# MCU_Sensors_CAN.net
KiCad netlist of a schematic drawn in Altium Designer
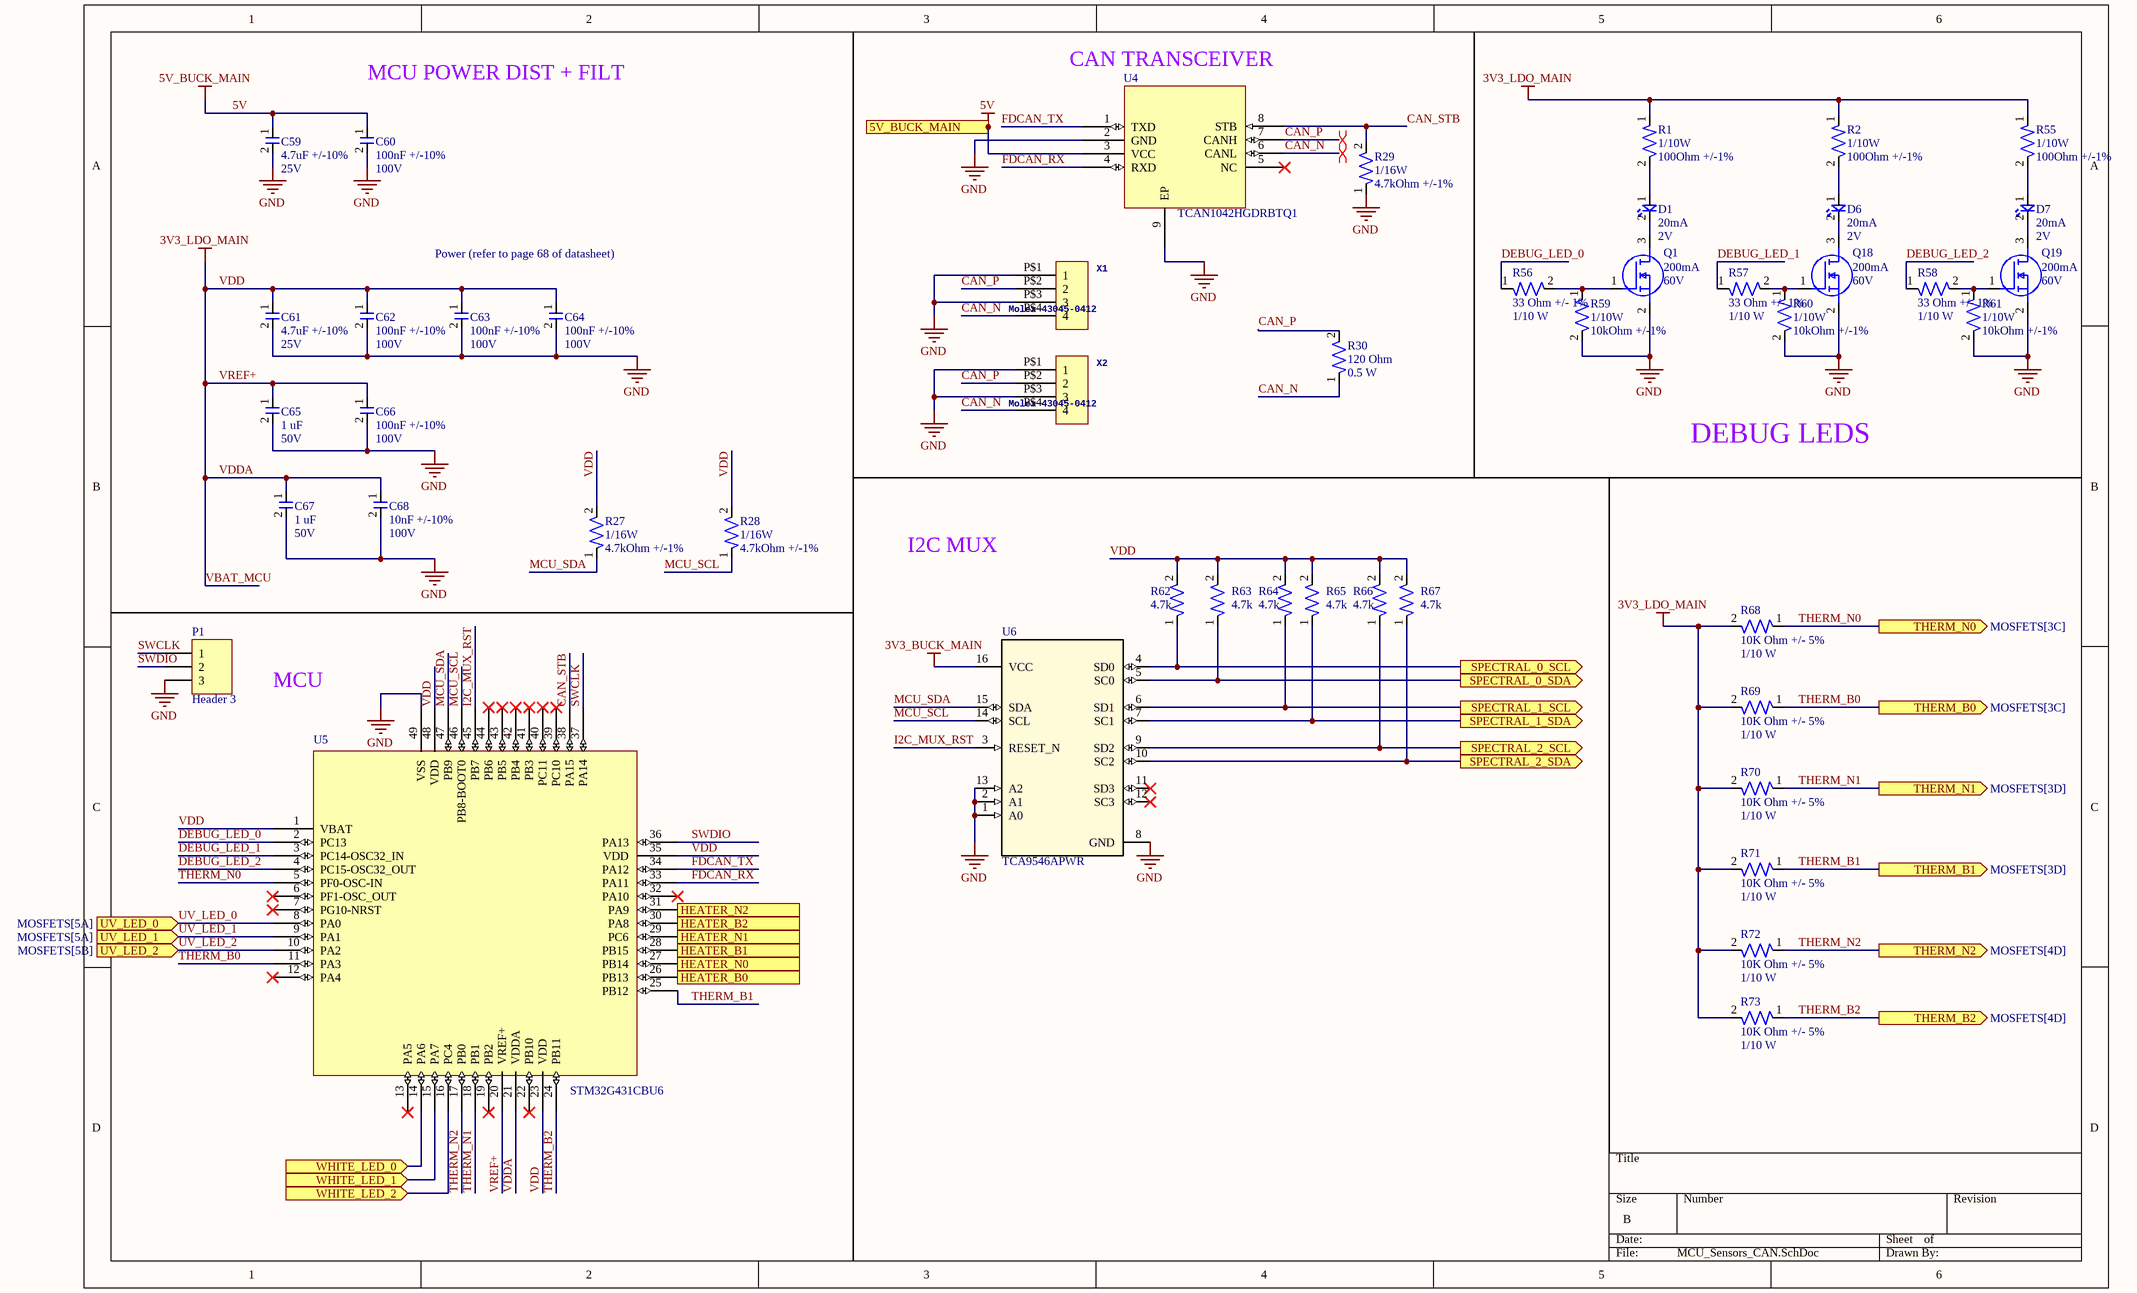
[diagram p0: MCU_Sensors_CAN.SchDoc]

(export (version "E")
  (design (tool "Eeschema 10.0.6"))
  (components
    (comp (ref "C59")
      (value "TMK107BBJ475KA-T")
      (footprint "CAP-0603")
      (description "4.7 µF ±10% 25V Ceramic Capacitor X5R 0603 (1608 Metric)")
      (fields
        (field (name "MANUFACTURER") "Taiyo Yuden")
        (field (name "CAPACITANCE") "4.7uF +/-10%")
        (field (name "VOLTAGE RATING") "25V")
      )
      (libsource (lib "MasterLib") (part "CAP-4.7U-0001"))
    )
    (comp (ref "C60")
      (value "CC0603KRX7R0BB104")
      (footprint "CAP-0603")
      (description "CAP CER 0.1UF 100V X7R 0603")
      (fields
        (field (name "MANUFACTURER") "YAGEO")
        (field (name "CAPACITANCE") "100nF +/-10%")
        (field (name "VOLTAGE RATING") "100V")
      )
      (libsource (lib "MasterLib") (part "CAP-100N-0001"))
    )
    (comp (ref "C61")
      (value "TMK107BBJ475KA-T")
      (footprint "CAP-0603")
      (description "4.7 µF ±10% 25V Ceramic Capacitor X5R 0603 (1608 Metric)")
      (fields
        (field (name "MANUFACTURER") "Taiyo Yuden")
        (field (name "CAPACITANCE") "4.7uF +/-10%")
        (field (name "VOLTAGE RATING") "25V")
      )
      (libsource (lib "MasterLib") (part "CAP-4.7U-0001"))
    )
    (comp (ref "C62")
      (value "CC0603KRX7R0BB104")
      (footprint "CAP-0603")
      (description "CAP CER 0.1UF 100V X7R 0603")
      (fields
        (field (name "MANUFACTURER") "YAGEO")
        (field (name "CAPACITANCE") "100nF +/-10%")
        (field (name "VOLTAGE RATING") "100V")
      )
      (libsource (lib "MasterLib") (part "CAP-100N-0001"))
    )
    (comp (ref "C63")
      (value "CC0603KRX7R0BB104")
      (footprint "CAP-0603")
      (description "CAP CER 0.1UF 100V X7R 0603")
      (fields
        (field (name "MANUFACTURER") "YAGEO")
        (field (name "CAPACITANCE") "100nF +/-10%")
        (field (name "VOLTAGE RATING") "100V")
      )
      (libsource (lib "MasterLib") (part "CAP-100N-0001"))
    )
    (comp (ref "C64")
      (value "CC0603KRX7R0BB104")
      (footprint "CAP-0603")
      (description "CAP CER 0.1UF 100V X7R 0603")
      (fields
        (field (name "MANUFACTURER") "YAGEO")
        (field (name "CAPACITANCE") "100nF +/-10%")
        (field (name "VOLTAGE RATING") "100V")
      )
      (libsource (lib "MasterLib") (part "CAP-100N-0001"))
    )
    (comp (ref "C65")
      (value "UMK107AB7105KA-T")
      (footprint "CAP-0603")
      (description "1 µF ±10% 50V Ceramic Capacitor X7R 0603 (1608 Metric)")
      (fields (field (name "CAPACITANCE") "1 uF") (field (name "VOLTAGE") "50V"))
      (libsource (lib "MasterLib") (part "CAP-1U-0002"))
    )
    (comp (ref "C66")
      (value "CC0603KRX7R0BB104")
      (footprint "CAP-0603")
      (description "CAP CER 0.1UF 100V X7R 0603")
      (fields
        (field (name "MANUFACTURER") "YAGEO")
        (field (name "CAPACITANCE") "100nF +/-10%")
        (field (name "VOLTAGE RATING") "100V")
      )
      (libsource (lib "MasterLib") (part "CAP-100N-0001"))
    )
    (comp (ref "C67")
      (value "UMK107AB7105KA-T")
      (footprint "CAP-0603")
      (description "1 µF ±10% 50V Ceramic Capacitor X7R 0603 (1608 Metric)")
      (fields (field (name "CAPACITANCE") "1 uF") (field (name "VOLTAGE") "50V"))
      (libsource (lib "MasterLib") (part "CAP-1U-0002"))
    )
    (comp (ref "C68")
      (value "CC0402KRX7R0BB103")
      (footprint "CAP-0402")
      (description "10000 pF ±10% 100V Ceramic Capacitor X7R 0402 (1005 Metric)")
      (fields
        (field (name "MANUFACTURER") "YAGEO")
        (field (name "CAPACITANCE") "10nF +/-10%")
        (field (name "VOLTAGE RATING") "100V")
      )
      (libsource (lib "MasterLib") (part "CAP-10N-0001"))
    )
    (comp (ref "D1")
      (value "150060AS75000")
      (footprint "LED-0603")
      (description "CAP CER 0.1UF 100V X7R 0603")
      (fields
        (field (name "MANUFACTURER") "Wurth Electronik")
        (field (name "CURRENT RATING") "20mA")
        (field (name "VF") "2V")
      )
      (libsource (lib "MasterLib") (part "LED_Amber_0001"))
    )
    (comp (ref "D6")
      (value "150060AS75000")
      (footprint "LED-0603")
      (description "CAP CER 0.1UF 100V X7R 0603")
      (fields
        (field (name "MANUFACTURER") "Wurth Electronik")
        (field (name "CURRENT RATING") "20mA")
        (field (name "VF") "2V")
      )
      (libsource (lib "MasterLib") (part "LED_Amber_0001"))
    )
    (comp (ref "D7")
      (value "150060AS75000")
      (footprint "LED-0603")
      (description "CAP CER 0.1UF 100V X7R 0603")
      (fields
        (field (name "MANUFACTURER") "Wurth Electronik")
        (field (name "CURRENT RATING") "20mA")
        (field (name "VF") "2V")
      )
      (libsource (lib "MasterLib") (part "LED_Amber_0001"))
    )
    (comp (ref "P1")
      (value "Header 3")
      (footprint "HDR1X3")
      (description "Header, 3-Pin")
      (fields (field (name "PUBLISHER") "Altium Limited"))
      (libsource (lib "Miscellaneous Connectors") (part "Header 3"))
    )
    (comp (ref "Q1")
      (value "T2N7002AK,LM")
      (footprint "NMOS-SOT23-3")
      (description "MOSFET N-CH 60V 200MA SOT23")
      (fields
        (field (name "MANUFACTURER") "Toshiba")
        (field (name "ID-CONTINUOUS") "200mA")
        (field (name "VDS-MAX") "60V")
      )
      (libsource (lib "MasterLib") (part "NMOS-200MA-0001"))
    )
    (comp (ref "Q18")
      (value "T2N7002AK,LM")
      (footprint "NMOS-SOT23-3")
      (description "MOSFET N-CH 60V 200MA SOT23")
      (fields
        (field (name "MANUFACTURER") "Toshiba")
        (field (name "ID-CONTINUOUS") "200mA")
        (field (name "VDS-MAX") "60V")
      )
      (libsource (lib "MasterLib") (part "NMOS-200MA-0001"))
    )
    (comp (ref "Q19")
      (value "T2N7002AK,LM")
      (footprint "NMOS-SOT23-3")
      (description "MOSFET N-CH 60V 200MA SOT23")
      (fields
        (field (name "MANUFACTURER") "Toshiba")
        (field (name "ID-CONTINUOUS") "200mA")
        (field (name "VDS-MAX") "60V")
      )
      (libsource (lib "MasterLib") (part "NMOS-200MA-0001"))
    )
    (comp (ref "R1")
      (value "AC0603FR-10100RL")
      (footprint "RES-0603")
      (description "100 Ohms ±1% 0.1W, 1/10W Chip Resistor 0603 (1608 Metric) Automotive AEC-Q200 Thick Film")
      (fields
        (field (name "MANUFACTURER") "YAGEO")
        (field (name "POWER RATING") "1/10W")
        (field (name "RESISTANCE") "100Ohm +/-1%")
      )
      (libsource (lib "MasterLib") (part "RES-100-0002"))
    )
    (comp (ref "R2")
      (value "AC0603FR-10100RL")
      (footprint "RES-0603")
      (description "100 Ohms ±1% 0.1W, 1/10W Chip Resistor 0603 (1608 Metric) Automotive AEC-Q200 Thick Film")
      (fields
        (field (name "MANUFACTURER") "YAGEO")
        (field (name "POWER RATING") "1/10W")
        (field (name "RESISTANCE") "100Ohm +/-1%")
      )
      (libsource (lib "MasterLib") (part "RES-100-0002"))
    )
    (comp (ref "R27")
      (value "RC0402FR-074K7P")
      (footprint "RES-0402")
      (description "RES SMD 4.7K OHM 1% 1/16W 0402")
      (fields
        (field (name "MANUFACTURER") "YAGEO")
        (field (name "POWER RATING") "1/16W")
        (field (name "RESISTANCE") "4.7kOhm +/-1%")
      )
      (libsource (lib "MasterLib") (part "RES-4.7K-0001"))
    )
    (comp (ref "R28")
      (value "RC0402FR-074K7P")
      (footprint "RES-0402")
      (description "RES SMD 4.7K OHM 1% 1/16W 0402")
      (fields
        (field (name "MANUFACTURER") "YAGEO")
        (field (name "POWER RATING") "1/16W")
        (field (name "RESISTANCE") "4.7kOhm +/-1%")
      )
      (libsource (lib "MasterLib") (part "RES-4.7K-0001"))
    )
    (comp (ref "R29")
      (value "RC0402FR-074K7P")
      (footprint "RES-0402")
      (description "RES SMD 4.7K OHM 1% 1/16W 0402")
      (fields
        (field (name "MANUFACTURER") "YAGEO")
        (field (name "POWER RATING") "1/16W")
        (field (name "RESISTANCE") "4.7kOhm +/-1%")
      )
      (libsource (lib "MasterLib") (part "RES-4.7K-0001"))
    )
    (comp (ref "R30")
      (value "CRGH1206F120R")
      (footprint "RES-1206")
      (description "120 Ohms ±1% 0.5W, 1/2W Chip Resistor 1206 (3216 Metric) Thick Film")
      (fields
        (field (name "TOLERANCE") "1%")
        (field (name "RESISTANCE") "120 Ohm")
        (field (name "POWER") "0.5 W")
      )
      (libsource (lib "MasterLib") (part "RES-120-0002"))
    )
    (comp (ref "R55")
      (value "AC0603FR-10100RL")
      (footprint "RES-0603")
      (description "100 Ohms ±1% 0.1W, 1/10W Chip Resistor 0603 (1608 Metric) Automotive AEC-Q200 Thick Film")
      (fields
        (field (name "MANUFACTURER") "YAGEO")
        (field (name "POWER RATING") "1/10W")
        (field (name "RESISTANCE") "100Ohm +/-1%")
      )
      (libsource (lib "MasterLib") (part "RES-100-0002"))
    )
    (comp (ref "R56")
      (value "ERJ2RKF33R0X")
      (footprint "RES-0402")
      (description "100mW Thick Film Resistors ±100ppm/℃ ±1% -55℃~+155℃ 33Ω 0402  Chip Resistor - Surface Mount ROHS")
      (fields
        (field (name "RESISTANCE") "33 Ohm +/- 1%")
        (field (name "POWER") "1/10 W")
        (field (name "JLC PART NUMBER") "C278594")
      )
      (libsource (lib "MasterLib") (part "RES-33-0003-JLC"))
    )
    (comp (ref "R57")
      (value "ERJ2RKF33R0X")
      (footprint "RES-0402")
      (description "100mW Thick Film Resistors ±100ppm/℃ ±1% -55℃~+155℃ 33Ω 0402  Chip Resistor - Surface Mount ROHS")
      (fields
        (field (name "RESISTANCE") "33 Ohm +/- 1%")
        (field (name "POWER") "1/10 W")
        (field (name "JLC PART NUMBER") "C278594")
      )
      (libsource (lib "MasterLib") (part "RES-33-0003-JLC"))
    )
    (comp (ref "R58")
      (value "ERJ2RKF33R0X")
      (footprint "RES-0402")
      (description "100mW Thick Film Resistors ±100ppm/℃ ±1% -55℃~+155℃ 33Ω 0402  Chip Resistor - Surface Mount ROHS")
      (fields
        (field (name "RESISTANCE") "33 Ohm +/- 1%")
        (field (name "POWER") "1/10 W")
        (field (name "JLC PART NUMBER") "C278594")
      )
      (libsource (lib "MasterLib") (part "RES-33-0003-JLC"))
    )
    (comp (ref "R59")
      (value "RC0603FR-0710KP")
      (footprint "RES-0603")
      (description "RES SMD 10K OHM 1% 1/10W 0603")
      (fields
        (field (name "MANUFACTURER") "YAGEO")
        (field (name "POWER RATING") "1/10W")
        (field (name "RESISTANCE") "10kOhm +/-1%")
      )
      (libsource (lib "MasterLib") (part "RES-10K-0002"))
    )
    (comp (ref "R60")
      (value "RC0603FR-0710KP")
      (footprint "RES-0603")
      (description "RES SMD 10K OHM 1% 1/10W 0603")
      (fields
        (field (name "MANUFACTURER") "YAGEO")
        (field (name "POWER RATING") "1/10W")
        (field (name "RESISTANCE") "10kOhm +/-1%")
      )
      (libsource (lib "MasterLib") (part "RES-10K-0002"))
    )
    (comp (ref "R61")
      (value "RC0603FR-0710KP")
      (footprint "RES-0603")
      (description "RES SMD 10K OHM 1% 1/10W 0603")
      (fields
        (field (name "MANUFACTURER") "YAGEO")
        (field (name "POWER RATING") "1/10W")
        (field (name "RESISTANCE") "10kOhm +/-1%")
      )
      (libsource (lib "MasterLib") (part "RES-10K-0002"))
    )
    (comp (ref "R62")
      (value "RC0402FR-074K7P")
      (footprint "RES-0402")
      (description "RES SMD 4.7K OHM 1% 1/16W 0402")
      (fields (field (name "MANUFACTURER") "YAGEO") (field (name "RESISTANCE") "4.7k"))
      (libsource (lib "MasterLib") (part "RES-4.7K-0001"))
    )
    (comp (ref "R63")
      (value "RC0402FR-074K7P")
      (footprint "RES-0402")
      (description "RES SMD 4.7K OHM 1% 1/16W 0402")
      (fields (field (name "MANUFACTURER") "YAGEO") (field (name "RESISTANCE") "4.7k"))
      (libsource (lib "MasterLib") (part "RES-4.7K-0001"))
    )
    (comp (ref "R64")
      (value "RC0402FR-074K7P")
      (footprint "RES-0402")
      (description "RES SMD 4.7K OHM 1% 1/16W 0402")
      (fields (field (name "MANUFACTURER") "YAGEO") (field (name "RESISTANCE") "4.7k"))
      (libsource (lib "MasterLib") (part "RES-4.7K-0001"))
    )
    (comp (ref "R65")
      (value "RC0402FR-074K7P")
      (footprint "RES-0402")
      (description "RES SMD 4.7K OHM 1% 1/16W 0402")
      (fields (field (name "MANUFACTURER") "YAGEO") (field (name "RESISTANCE") "4.7k"))
      (libsource (lib "MasterLib") (part "RES-4.7K-0001"))
    )
    (comp (ref "R66")
      (value "RC0402FR-074K7P")
      (footprint "RES-0402")
      (description "RES SMD 4.7K OHM 1% 1/16W 0402")
      (fields (field (name "MANUFACTURER") "YAGEO") (field (name "RESISTANCE") "4.7k"))
      (libsource (lib "MasterLib") (part "RES-4.7K-0001"))
    )
    (comp (ref "R67")
      (value "RC0402FR-074K7P")
      (footprint "RES-0402")
      (description "RES SMD 4.7K OHM 1% 1/16W 0402")
      (fields (field (name "MANUFACTURER") "YAGEO") (field (name "RESISTANCE") "4.7k"))
      (libsource (lib "MasterLib") (part "RES-4.7K-0001"))
    )
    (comp (ref "R68")
      (value "ERJ2GEJ103X")
      (footprint "RES-0402")
      (fields
        (field (name "RESISTANCE") "10K Ohm +/- 5%")
        (field (name "POWER") "1/10 W")
        (field (name "JLC PART NUMBER") "C278577")
      )
      (libsource (lib "MasterLib") (part "RES-10K-0003-JLC"))
    )
    (comp (ref "R69")
      (value "ERJ2GEJ103X")
      (footprint "RES-0402")
      (fields
        (field (name "RESISTANCE") "10K Ohm +/- 5%")
        (field (name "POWER") "1/10 W")
        (field (name "JLC PART NUMBER") "C278577")
      )
      (libsource (lib "MasterLib") (part "RES-10K-0003-JLC"))
    )
    (comp (ref "R70")
      (value "ERJ2GEJ103X")
      (footprint "RES-0402")
      (fields
        (field (name "RESISTANCE") "10K Ohm +/- 5%")
        (field (name "POWER") "1/10 W")
        (field (name "JLC PART NUMBER") "C278577")
      )
      (libsource (lib "MasterLib") (part "RES-10K-0003-JLC"))
    )
    (comp (ref "R71")
      (value "ERJ2GEJ103X")
      (footprint "RES-0402")
      (fields
        (field (name "RESISTANCE") "10K Ohm +/- 5%")
        (field (name "POWER") "1/10 W")
        (field (name "JLC PART NUMBER") "C278577")
      )
      (libsource (lib "MasterLib") (part "RES-10K-0003-JLC"))
    )
    (comp (ref "R72")
      (value "ERJ2GEJ103X")
      (footprint "RES-0402")
      (fields
        (field (name "RESISTANCE") "10K Ohm +/- 5%")
        (field (name "POWER") "1/10 W")
        (field (name "JLC PART NUMBER") "C278577")
      )
      (libsource (lib "MasterLib") (part "RES-10K-0003-JLC"))
    )
    (comp (ref "R73")
      (value "ERJ2GEJ103X")
      (footprint "RES-0402")
      (fields
        (field (name "RESISTANCE") "10K Ohm +/- 5%")
        (field (name "POWER") "1/10 W")
        (field (name "JLC PART NUMBER") "C278577")
      )
      (libsource (lib "MasterLib") (part "RES-10K-0003-JLC"))
    )
    (comp (ref "U4")
      (value "TCAN1042HGDRBTQ1")
      (footprint "IC-8-VSON")
      (description "1/1 Transceiver CANbus 8-VSON (3x3)")
      (fields (field (name "MANUFACTURER") "Texas Instrument"))
      (libsource (lib "MasterLib") (part "IC-CAN-TRANSCEIVER-0002"))
    )
    (comp (ref "U5")
      (value "STM32G431CBU6")
      (footprint "MCU-UFQFPN48")
      (libsource (lib "MasterLib") (part "IC-STM32G431CBU6"))
    )
    (comp (ref "U6")
      (value "TCA9546APWR")
      (footprint "PW0016A-IPC_A")
      (description "Multiplexer Switch ICs I2C SWITCH 4CH")
      (fields (field (name "COPYRIGHT") "Copyright (C) 2023 Ultra Librarian. All rights reserved."))
      (libsource (lib "MasterLib") (part "IC-MUX-0003"))
    )
    (comp (ref "X1")
      (value "Molex 43045-0412")
      (footprint "43045-0412")
      (libsource (lib "Molex Microfit") (part "Micro-Fit Molex 4 Pin 2 Row Vertical"))
    )
    (comp (ref "X2")
      (value "Molex 43045-0412")
      (footprint "43045-0412")
      (libsource (lib "Molex Microfit") (part "Micro-Fit Molex 4 Pin 2 Row Vertical"))
    )
  )
  (nets
    (net (code "1") (name "/CAN_N") (class "Default")
      (node (ref "R30") (pin "1") (pinfunction "1_1") (pintype "passive"))
      (node (ref "U4") (pin "6") (pinfunction "CANL_6") (pintype "bidirectional"))
      (node (ref "X1") (pin "P$4") (pinfunction "4_P$4") (pintype "passive"))
      (node (ref "X2") (pin "P$4") (pinfunction "4_P$4") (pintype "passive"))
    )
    (net (code "2") (name "/CAN_P") (class "Default")
      (node (ref "R30") (pin "2") (pinfunction "2_2") (pintype "passive"))
      (node (ref "U4") (pin "7") (pinfunction "CANH_7") (pintype "bidirectional"))
      (node (ref "X1") (pin "P$2") (pinfunction "2_P$2") (pintype "passive"))
      (node (ref "X2") (pin "P$2") (pinfunction "2_P$2") (pintype "passive"))
    )
    (net (code "3") (name "/CAN_STB") (class "Default")
      (node (ref "R29") (pin "2") (pinfunction "2_2") (pintype "passive"))
      (node (ref "U4") (pin "8") (pinfunction "STB_8") (pintype "input"))
      (node (ref "U5") (pin "38") (pinfunction "PA15_38") (pintype "bidirectional"))
    )
    (net (code "4") (name "/DEBUG_LED_0") (class "Default")
      (node (ref "R56") (pin "1") (pinfunction "1_1") (pintype "passive"))
      (node (ref "U5") (pin "2") (pinfunction "PC13_2") (pintype "bidirectional"))
    )
    (net (code "5") (name "/DEBUG_LED_1") (class "Default")
      (node (ref "R57") (pin "1") (pinfunction "1_1") (pintype "passive"))
      (node (ref "U5") (pin "3") (pinfunction "PC14-OSC32_IN_3") (pintype "bidirectional"))
    )
    (net (code "6") (name "/DEBUG_LED_2") (class "Default")
      (node (ref "R58") (pin "1") (pinfunction "1_1") (pintype "passive"))
      (node (ref "U5") (pin "4") (pinfunction "PC15-OSC32_OUT_4") (pintype "bidirectional"))
    )
    (net (code "7") (name "/FDCAN_RX") (class "Default")
      (node (ref "U4") (pin "4") (pinfunction "RXD_4") (pintype "bidirectional"))
      (node (ref "U5") (pin "33") (pinfunction "PA11_33") (pintype "bidirectional"))
    )
    (net (code "8") (name "/FDCAN_TX") (class "Default")
      (node (ref "U4") (pin "1") (pinfunction "TXD_1") (pintype "bidirectional"))
      (node (ref "U5") (pin "34") (pinfunction "PA12_34") (pintype "bidirectional"))
    )
    (net (code "9") (name "/HEATER_B0") (class "Default")
      (node (ref "U5") (pin "26") (pinfunction "PB13_26") (pintype "bidirectional"))
    )
    (net (code "10") (name "/HEATER_B1") (class "Default")
      (node (ref "U5") (pin "28") (pinfunction "PB15_28") (pintype "bidirectional"))
    )
    (net (code "11") (name "/HEATER_B2") (class "Default")
      (node (ref "U5") (pin "30") (pinfunction "PA8_30") (pintype "bidirectional"))
    )
    (net (code "12") (name "/HEATER_N0") (class "Default")
      (node (ref "U5") (pin "27") (pinfunction "PB14_27") (pintype "bidirectional"))
    )
    (net (code "13") (name "/HEATER_N1") (class "Default")
      (node (ref "U5") (pin "29") (pinfunction "PC6_29") (pintype "bidirectional"))
    )
    (net (code "14") (name "/HEATER_N2") (class "Default")
      (node (ref "U5") (pin "31") (pinfunction "PA9_31") (pintype "bidirectional"))
    )
    (net (code "15") (name "/I2C_MUX_RST") (class "Default")
      (node (ref "U5") (pin "45") (pinfunction "PB7_45") (pintype "bidirectional"))
      (node (ref "U6") (pin "3") (pinfunction "RESET_N_3") (pintype "input"))
    )
    (net (code "16") (name "/MCU_SCL") (class "Default")
      (node (ref "R28") (pin "1") (pinfunction "1_1") (pintype "passive"))
      (node (ref "U5") (pin "46") (pinfunction "PB8-BOOT0_46") (pintype "bidirectional"))
      (node (ref "U6") (pin "14") (pinfunction "SCL_14") (pintype "bidirectional"))
    )
    (net (code "17") (name "/MCU_SDA") (class "Default")
      (node (ref "R27") (pin "1") (pinfunction "1_1") (pintype "passive"))
      (node (ref "U5") (pin "47") (pinfunction "PB9_47") (pintype "bidirectional"))
      (node (ref "U6") (pin "15") (pinfunction "SDA_15") (pintype "bidirectional"))
    )
    (net (code "18") (name "/SPECTRAL_0_SCL") (class "Default")
      (node (ref "R62") (pin "1") (pinfunction "1_1") (pintype "passive"))
      (node (ref "U6") (pin "4") (pinfunction "SD0_4") (pintype "bidirectional"))
    )
    (net (code "19") (name "/SPECTRAL_0_SDA") (class "Default")
      (node (ref "R63") (pin "1") (pinfunction "1_1") (pintype "passive"))
      (node (ref "U6") (pin "5") (pinfunction "SC0_5") (pintype "bidirectional"))
    )
    (net (code "20") (name "/SPECTRAL_1_SCL") (class "Default")
      (node (ref "R64") (pin "1") (pinfunction "1_1") (pintype "passive"))
      (node (ref "U6") (pin "6") (pinfunction "SD1_6") (pintype "bidirectional"))
    )
    (net (code "21") (name "/SPECTRAL_1_SDA") (class "Default")
      (node (ref "R65") (pin "1") (pinfunction "1_1") (pintype "passive"))
      (node (ref "U6") (pin "7") (pinfunction "SC1_7") (pintype "bidirectional"))
    )
    (net (code "22") (name "/SPECTRAL_2_SCL") (class "Default")
      (node (ref "R66") (pin "1") (pinfunction "1_1") (pintype "passive"))
      (node (ref "U6") (pin "9") (pinfunction "SD2_9") (pintype "bidirectional"))
    )
    (net (code "23") (name "/SPECTRAL_2_SDA") (class "Default")
      (node (ref "R67") (pin "1") (pinfunction "1_1") (pintype "passive"))
      (node (ref "U6") (pin "10") (pinfunction "SC2_10") (pintype "bidirectional"))
    )
    (net (code "24") (name "/SWCLK") (class "Default")
      (node (ref "P1") (pin "1") (pinfunction "1_1") (pintype "passive"))
      (node (ref "U5") (pin "37") (pinfunction "PA14_37") (pintype "bidirectional"))
    )
    (net (code "25") (name "/SWDIO") (class "Default")
      (node (ref "P1") (pin "2") (pinfunction "2_2") (pintype "passive"))
      (node (ref "U5") (pin "36") (pinfunction "PA13_36") (pintype "bidirectional"))
    )
    (net (code "26") (name "/THERM_B0") (class "Default")
      (node (ref "R69") (pin "1") (pinfunction "1_1") (pintype "passive"))
      (node (ref "U5") (pin "11") (pinfunction "PA3_11") (pintype "bidirectional"))
    )
    (net (code "27") (name "/THERM_B1") (class "Default")
      (node (ref "R71") (pin "1") (pinfunction "1_1") (pintype "passive"))
      (node (ref "U5") (pin "25") (pinfunction "PB12_25") (pintype "bidirectional"))
    )
    (net (code "28") (name "/THERM_B2") (class "Default")
      (node (ref "R73") (pin "1") (pinfunction "1_1") (pintype "passive"))
      (node (ref "U5") (pin "24") (pinfunction "PB11_24") (pintype "bidirectional"))
    )
    (net (code "29") (name "/THERM_N0") (class "Default")
      (node (ref "R68") (pin "1") (pinfunction "1_1") (pintype "passive"))
      (node (ref "U5") (pin "5") (pinfunction "PF0-OSC-IN_5") (pintype "bidirectional"))
    )
    (net (code "30") (name "/THERM_N1") (class "Default")
      (node (ref "R70") (pin "1") (pinfunction "1_1") (pintype "passive"))
      (node (ref "U5") (pin "18") (pinfunction "PB1_18") (pintype "bidirectional"))
    )
    (net (code "31") (name "/THERM_N2") (class "Default")
      (node (ref "R72") (pin "1") (pinfunction "1_1") (pintype "passive"))
      (node (ref "U5") (pin "17") (pinfunction "PB0_17") (pintype "bidirectional"))
    )
    (net (code "32") (name "/UV_LED_0") (class "Default")
      (node (ref "U5") (pin "8") (pinfunction "PA0_8") (pintype "bidirectional"))
    )
    (net (code "33") (name "/UV_LED_1") (class "Default")
      (node (ref "U5") (pin "9") (pinfunction "PA1_9") (pintype "bidirectional"))
    )
    (net (code "34") (name "/UV_LED_2") (class "Default")
      (node (ref "U5") (pin "10") (pinfunction "PA2_10") (pintype "bidirectional"))
    )
    (net (code "35") (name "/WHITE_LED_0") (class "Default")
      (node (ref "U5") (pin "14") (pinfunction "PA6_14") (pintype "bidirectional"))
    )
    (net (code "36") (name "/WHITE_LED_1") (class "Default")
      (node (ref "U5") (pin "15") (pinfunction "PA7_15") (pintype "bidirectional"))
    )
    (net (code "37") (name "/WHITE_LED_2") (class "Default")
      (node (ref "U5") (pin "16") (pinfunction "PC4_16") (pintype "bidirectional"))
    )
    (net (code "38") (name "3V3_BUCK_MAIN") (class "Default")
      (node (ref "U6") (pin "16") (pinfunction "VCC_16") (pintype "power_in"))
    )
    (net (code "39") (name "3V3_LDO_MAIN") (class "Default")
      (node (ref "C61") (pin "1") (pinfunction "1_1") (pintype "passive"))
      (node (ref "C62") (pin "1") (pinfunction "1_1") (pintype "passive"))
      (node (ref "C63") (pin "1") (pinfunction "1_1") (pintype "passive"))
      (node (ref "C64") (pin "1") (pinfunction "1_1") (pintype "passive"))
      (node (ref "C65") (pin "1") (pinfunction "1_1") (pintype "passive"))
      (node (ref "C66") (pin "1") (pinfunction "1_1") (pintype "passive"))
      (node (ref "C67") (pin "1") (pinfunction "1_1") (pintype "passive"))
      (node (ref "C68") (pin "1") (pinfunction "1_1") (pintype "passive"))
      (node (ref "R1") (pin "1") (pinfunction "1_1") (pintype "passive"))
      (node (ref "R2") (pin "1") (pinfunction "1_1") (pintype "passive"))
      (node (ref "R27") (pin "2") (pinfunction "2_2") (pintype "passive"))
      (node (ref "R28") (pin "2") (pinfunction "2_2") (pintype "passive"))
      (node (ref "R55") (pin "1") (pinfunction "1_1") (pintype "passive"))
      (node (ref "R62") (pin "2") (pinfunction "2_2") (pintype "passive"))
      (node (ref "R63") (pin "2") (pinfunction "2_2") (pintype "passive"))
      (node (ref "R64") (pin "2") (pinfunction "2_2") (pintype "passive"))
      (node (ref "R65") (pin "2") (pinfunction "2_2") (pintype "passive"))
      (node (ref "R66") (pin "2") (pinfunction "2_2") (pintype "passive"))
      (node (ref "R67") (pin "2") (pinfunction "2_2") (pintype "passive"))
      (node (ref "R68") (pin "2") (pinfunction "2_2") (pintype "passive"))
      (node (ref "R69") (pin "2") (pinfunction "2_2") (pintype "passive"))
      (node (ref "R70") (pin "2") (pinfunction "2_2") (pintype "passive"))
      (node (ref "R71") (pin "2") (pinfunction "2_2") (pintype "passive"))
      (node (ref "R72") (pin "2") (pinfunction "2_2") (pintype "passive"))
      (node (ref "R73") (pin "2") (pinfunction "2_2") (pintype "passive"))
      (node (ref "U5") (pin "1") (pinfunction "VBAT_1") (pintype "power_in"))
      (node (ref "U5") (pin "20") (pinfunction "VREF+_20") (pintype "power_in"))
      (node (ref "U5") (pin "21") (pinfunction "VDDA_21") (pintype "power_in"))
      (node (ref "U5") (pin "23") (pinfunction "VDD_23") (pintype "power_in"))
      (node (ref "U5") (pin "35") (pinfunction "VDD_35") (pintype "power_in"))
      (node (ref "U5") (pin "48") (pinfunction "VDD_48") (pintype "power_in"))
    )
    (net (code "40") (name "5V") (class "Default")
      (node (ref "C59") (pin "1") (pinfunction "1_1") (pintype "passive"))
      (node (ref "C60") (pin "1") (pinfunction "1_1") (pintype "passive"))
      (node (ref "U4") (pin "3") (pinfunction "VCC_3") (pintype "power_in"))
    )
    (net (code "41") (name "GND") (class "Default")
      (node (ref "C59") (pin "2") (pinfunction "2_2") (pintype "passive"))
      (node (ref "C60") (pin "2") (pinfunction "2_2") (pintype "passive"))
      (node (ref "C61") (pin "2") (pinfunction "2_2") (pintype "passive"))
      (node (ref "C62") (pin "2") (pinfunction "2_2") (pintype "passive"))
      (node (ref "C63") (pin "2") (pinfunction "2_2") (pintype "passive"))
      (node (ref "C64") (pin "2") (pinfunction "2_2") (pintype "passive"))
      (node (ref "C65") (pin "2") (pinfunction "2_2") (pintype "passive"))
      (node (ref "C66") (pin "2") (pinfunction "2_2") (pintype "passive"))
      (node (ref "C67") (pin "2") (pinfunction "2_2") (pintype "passive"))
      (node (ref "C68") (pin "2") (pinfunction "2_2") (pintype "passive"))
      (node (ref "P1") (pin "3") (pinfunction "3_3") (pintype "passive"))
      (node (ref "Q1") (pin "2") (pinfunction "S_2") (pintype "passive"))
      (node (ref "Q18") (pin "2") (pinfunction "S_2") (pintype "passive"))
      (node (ref "Q19") (pin "2") (pinfunction "S_2") (pintype "passive"))
      (node (ref "R29") (pin "1") (pinfunction "1_1") (pintype "passive"))
      (node (ref "R59") (pin "2") (pinfunction "2_2") (pintype "passive"))
      (node (ref "R60") (pin "2") (pinfunction "2_2") (pintype "passive"))
      (node (ref "R61") (pin "2") (pinfunction "2_2") (pintype "passive"))
      (node (ref "U4") (pin "2") (pinfunction "GND_2") (pintype "power_in"))
      (node (ref "U4") (pin "9") (pinfunction "EP_9") (pintype "power_in"))
      (node (ref "U5") (pin "49") (pinfunction "VSS_49") (pintype "power_in"))
      (node (ref "U6") (pin "1") (pinfunction "A0_1") (pintype "input"))
      (node (ref "U6") (pin "13") (pinfunction "A2_13") (pintype "input"))
      (node (ref "U6") (pin "2") (pinfunction "A1_2") (pintype "input"))
      (node (ref "U6") (pin "8") (pinfunction "GND_8") (pintype "power_in"))
      (node (ref "X1") (pin "P$1") (pinfunction "1_P$1") (pintype "passive"))
      (node (ref "X1") (pin "P$3") (pinfunction "3_P$3") (pintype "passive"))
      (node (ref "X2") (pin "P$1") (pinfunction "1_P$1") (pintype "passive"))
      (node (ref "X2") (pin "P$3") (pinfunction "3_P$3") (pintype "passive"))
    )
    (net (code "42") (name "Net-(D1-Pad1)") (class "Default")
      (node (ref "D1") (pin "1") (pinfunction "1_1") (pintype "passive"))
      (node (ref "R1") (pin "2") (pinfunction "2_2") (pintype "passive"))
    )
    (net (code "43") (name "Net-(D6-Pad1)") (class "Default")
      (node (ref "D6") (pin "1") (pinfunction "1_1") (pintype "passive"))
      (node (ref "R2") (pin "2") (pinfunction "2_2") (pintype "passive"))
    )
    (net (code "44") (name "Net-(D7-Pad1)") (class "Default")
      (node (ref "D7") (pin "1") (pinfunction "1_1") (pintype "passive"))
      (node (ref "R55") (pin "2") (pinfunction "2_2") (pintype "passive"))
    )
    (net (code "45") (name "Net-(Q1-D)") (class "Default")
      (node (ref "D1") (pin "2") (pinfunction "2_2") (pintype "passive"))
      (node (ref "Q1") (pin "3") (pinfunction "D_3") (pintype "passive"))
    )
    (net (code "46") (name "Net-(Q1-G)") (class "Default")
      (node (ref "Q1") (pin "1") (pinfunction "G_1") (pintype "passive"))
      (node (ref "R56") (pin "2") (pinfunction "2_2") (pintype "passive"))
      (node (ref "R59") (pin "1") (pinfunction "1_1") (pintype "passive"))
    )
    (net (code "47") (name "Net-(Q18-D)") (class "Default")
      (node (ref "D6") (pin "2") (pinfunction "2_2") (pintype "passive"))
      (node (ref "Q18") (pin "3") (pinfunction "D_3") (pintype "passive"))
    )
    (net (code "48") (name "Net-(Q18-G)") (class "Default")
      (node (ref "Q18") (pin "1") (pinfunction "G_1") (pintype "passive"))
      (node (ref "R57") (pin "2") (pinfunction "2_2") (pintype "passive"))
      (node (ref "R60") (pin "1") (pinfunction "1_1") (pintype "passive"))
    )
    (net (code "49") (name "Net-(Q19-D)") (class "Default")
      (node (ref "D7") (pin "2") (pinfunction "2_2") (pintype "passive"))
      (node (ref "Q19") (pin "3") (pinfunction "D_3") (pintype "passive"))
    )
    (net (code "50") (name "Net-(Q19-G)") (class "Default")
      (node (ref "Q19") (pin "1") (pinfunction "G_1") (pintype "passive"))
      (node (ref "R58") (pin "2") (pinfunction "2_2") (pintype "passive"))
      (node (ref "R61") (pin "1") (pinfunction "1_1") (pintype "passive"))
    )
    (net (code "51") (name "unconnected-(U4-NC-Pad5)") (class "Default")
      (node (ref "U4") (pin "5") (pinfunction "NC_5") (pintype "power_in+no_connect"))
    )
    (net (code "52") (name "unconnected-(U5-PA4-Pad12)") (class "Default")
      (node (ref "U5") (pin "12") (pinfunction "PA4_12") (pintype "bidirectional+no_connect"))
    )
    (net (code "53") (name "unconnected-(U5-PA5-Pad13)") (class "Default")
      (node (ref "U5") (pin "13") (pinfunction "PA5_13") (pintype "bidirectional+no_connect"))
    )
    (net (code "54") (name "unconnected-(U5-PA10-Pad32)") (class "Default")
      (node (ref "U5") (pin "32") (pinfunction "PA10_32") (pintype "bidirectional+no_connect"))
    )
    (net (code "55") (name "unconnected-(U5-PB2-Pad19)") (class "Default")
      (node (ref "U5") (pin "19") (pinfunction "PB2_19") (pintype "bidirectional+no_connect"))
    )
    (net (code "56") (name "unconnected-(U5-PB3-Pad41)") (class "Default")
      (node (ref "U5") (pin "41") (pinfunction "PB3_41") (pintype "bidirectional+no_connect"))
    )
    (net (code "57") (name "unconnected-(U5-PB4-Pad42)") (class "Default")
      (node (ref "U5") (pin "42") (pinfunction "PB4_42") (pintype "bidirectional+no_connect"))
    )
    (net (code "58") (name "unconnected-(U5-PB5-Pad43)") (class "Default")
      (node (ref "U5") (pin "43") (pinfunction "PB5_43") (pintype "bidirectional+no_connect"))
    )
    (net (code "59") (name "unconnected-(U5-PB6-Pad44)") (class "Default")
      (node (ref "U5") (pin "44") (pinfunction "PB6_44") (pintype "bidirectional+no_connect"))
    )
    (net (code "60") (name "unconnected-(U5-PB10-Pad22)") (class "Default")
      (node (ref "U5") (pin "22") (pinfunction "PB10_22") (pintype "bidirectional+no_connect"))
    )
    (net (code "61") (name "unconnected-(U5-PC10-Pad39)") (class "Default")
      (node (ref "U5") (pin "39") (pinfunction "PC10_39") (pintype "bidirectional+no_connect"))
    )
    (net (code "62") (name "unconnected-(U5-PC11-Pad40)") (class "Default")
      (node (ref "U5") (pin "40") (pinfunction "PC11_40") (pintype "bidirectional+no_connect"))
    )
    (net (code "63") (name "unconnected-(U5-PF1-OSC_OUT-Pad6)") (class "Default")
      (node (ref "U5") (pin "6") (pinfunction "PF1-OSC_OUT_6") (pintype "bidirectional+no_connect"))
    )
    (net (code "64") (name "unconnected-(U5-PG10-NRST-Pad7)") (class "Default")
      (node (ref "U5") (pin "7") (pinfunction "PG10-NRST_7") (pintype "bidirectional+no_connect"))
    )
    (net (code "65") (name "unconnected-(U6-SC3-Pad12)") (class "Default")
      (node (ref "U6") (pin "12") (pinfunction "SC3_12") (pintype "bidirectional+no_connect"))
    )
    (net (code "66") (name "unconnected-(U6-SD3-Pad11)") (class "Default")
      (node (ref "U6") (pin "11") (pinfunction "SD3_11") (pintype "bidirectional+no_connect"))
    )
  )
)
